# S06_Sensors.net
KiCad netlist of a schematic drawn in Altium Designer
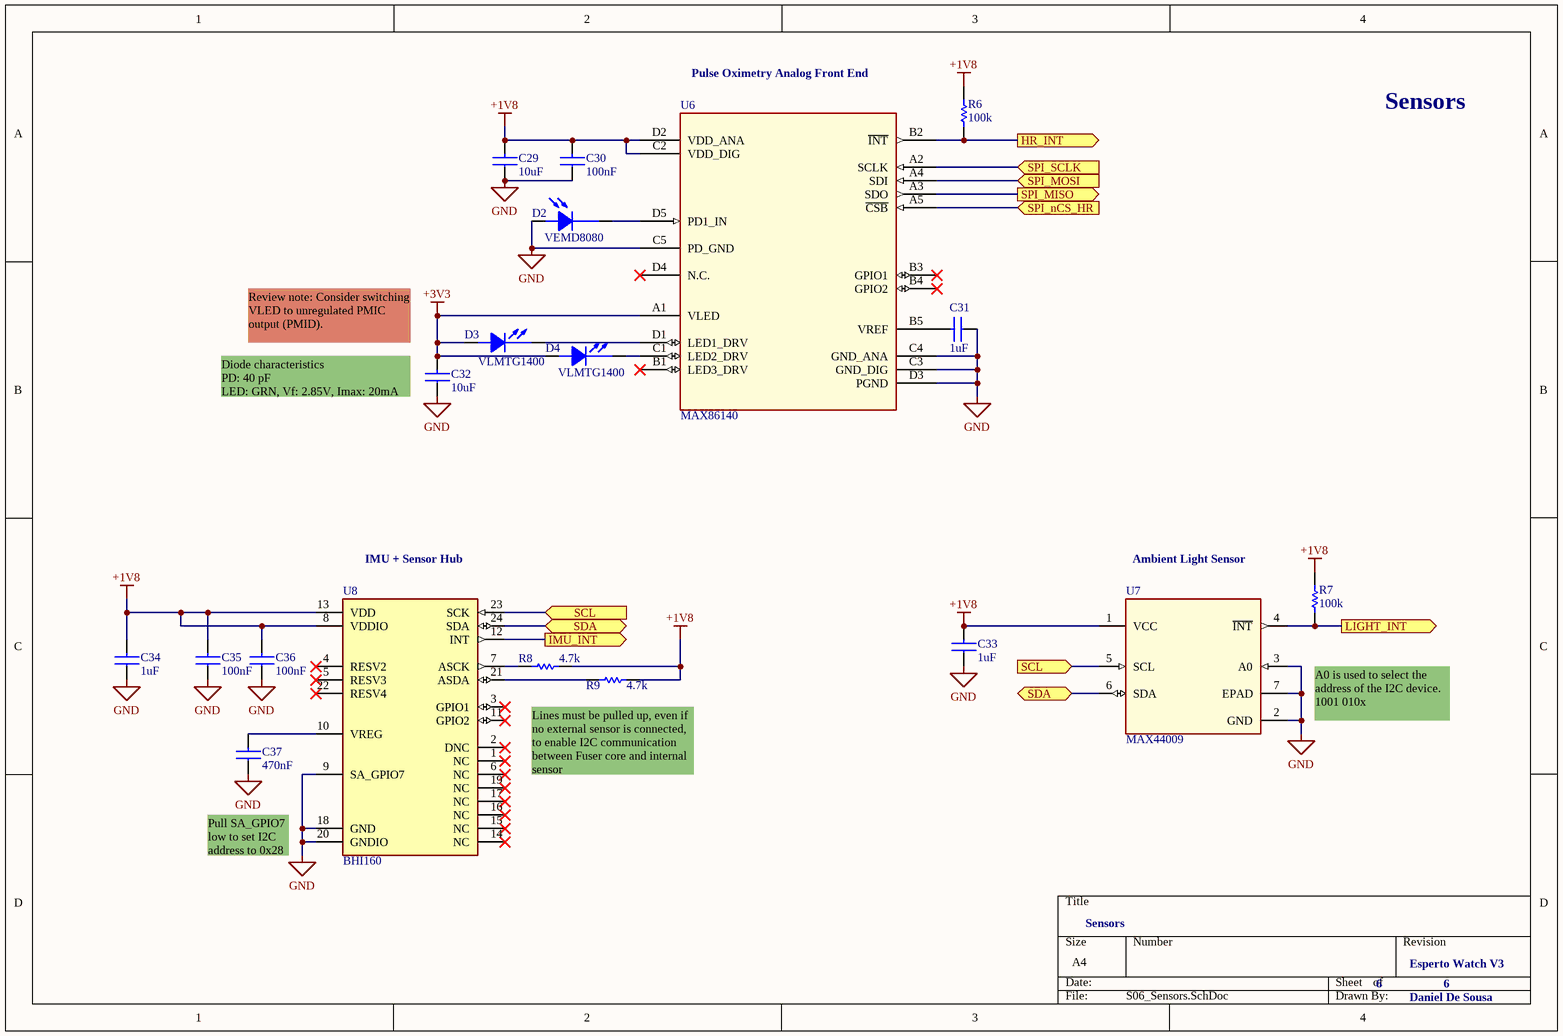
[diagram p0: S06_Sensors.SchDoc]

(export (version "E")
  (design (tool "Eeschema 10.0.6"))
  (components
    (comp (ref "C29")
      (value "10uF")
      (footprint "CC_1005_0402_N")
      (description "Capacitor")
      (libsource (lib "Esperto") (part "Capacitor"))
    )
    (comp (ref "C30")
      (value "100nF")
      (footprint "CC_1005_0402_N")
      (description "Capacitor")
      (libsource (lib "Esperto") (part "Capacitor"))
    )
    (comp (ref "C31")
      (value "1uF")
      (footprint "CC_1005_0402_N")
      (description "Capacitor")
      (libsource (lib "Esperto") (part "Capacitor"))
    )
    (comp (ref "C32")
      (value "10uF")
      (footprint "CC_1005_0402_N")
      (description "Capacitor")
      (libsource (lib "Esperto") (part "Capacitor"))
    )
    (comp (ref "C33")
      (value "1uF")
      (footprint "CC_1005_0402_N")
      (description "Capacitor")
      (libsource (lib "Esperto") (part "Capacitor"))
    )
    (comp (ref "C34")
      (value "1uF")
      (footprint "CC_1005_0402_N")
      (description "Capacitor")
      (libsource (lib "Esperto") (part "Capacitor"))
    )
    (comp (ref "C35")
      (value "100nF")
      (footprint "CC_1005_0402_N")
      (description "Capacitor")
      (libsource (lib "Esperto") (part "Capacitor"))
    )
    (comp (ref "C36")
      (value "100nF")
      (footprint "CC_1005_0402_N")
      (description "Capacitor")
      (libsource (lib "Esperto") (part "Capacitor"))
    )
    (comp (ref "C37")
      (value "470nF")
      (footprint "CC_1005_0402_N")
      (description "Capacitor")
      (libsource (lib "Esperto") (part "Capacitor"))
    )
    (comp (ref "D2")
      (value "VEMD8080")
      (footprint "VEMD8080")
      (description "Photodiode")
      (libsource (lib "Esperto") (part "Photodiode"))
    )
    (comp (ref "D3")
      (value "VLMTG1400")
      (footprint "LED_GREEN_0603")
      (description "Single LED")
      (libsource (lib "Esperto") (part "LED"))
    )
    (comp (ref "D4")
      (value "VLMTG1400")
      (footprint "LED_GREEN_0603")
      (description "Single LED")
      (libsource (lib "Esperto") (part "LED"))
    )
    (comp (ref "R6")
      (value "100k")
      (footprint "RC_1005_0402_N")
      (description "Resistor")
      (libsource (lib "Esperto") (part "Resistor"))
    )
    (comp (ref "R7")
      (value "100k")
      (footprint "RC_1005_0402_N")
      (description "Resistor")
      (libsource (lib "Esperto") (part "Resistor"))
    )
    (comp (ref "R8")
      (value "4.7k")
      (footprint "RC_1005_0402_N")
      (description "Resistor")
      (libsource (lib "Esperto") (part "Resistor"))
    )
    (comp (ref "R9")
      (value "4.7k")
      (footprint "RC_1005_0402_N")
      (description "Resistor")
      (libsource (lib "Esperto") (part "Resistor"))
    )
    (comp (ref "U6")
      (value "MAX86140")
      (footprint "MAX86140")
      (description "Optical Pulse Oximeter and\r\nHeart-Rate Sensor")
      (fields
        (field (name "MANUFACTURER_PART_NUMBER") "MAX86140ENP+")
        (field (name "COPYRIGHT") "Copyright (C) 2018 Accelerated Designs. All rights reserved")
      )
      (libsource (lib "Esperto") (part "MAX86140"))
    )
    (comp (ref "U7")
      (value "MAX44009")
      (footprint "MAX44009")
      (description "Ambient Light Sensor")
      (fields
        (field (name "MANUFACTURER_PART_NUMBER") "MAX44009EDT+T")
        (field (name "COPYRIGHT") "Copyright (C) 2018 Accelerated Designs. All rights reserved")
      )
      (libsource (lib "Esperto") (part "MAX44009"))
    )
    (comp (ref "U8")
      (value "BHI160")
      (footprint "BHI160")
      (description "Ultra low-power sensor hub incl. integrated IMU")
      (fields (field (name "PROVIDED BY") "BOSCH"))
      (libsource (lib "Esperto") (part "BHI160"))
    )
  )
  (nets
    (net (code "1") (name "+1V8") (class "Default")
      (node (ref "C29") (pin "2") (pinfunction "2_2") (pintype "passive"))
      (node (ref "C30") (pin "2") (pinfunction "2_2") (pintype "passive"))
      (node (ref "C33") (pin "2") (pinfunction "2_2") (pintype "passive"))
      (node (ref "C34") (pin "2") (pinfunction "2_2") (pintype "passive"))
      (node (ref "C35") (pin "2") (pinfunction "2_2") (pintype "passive"))
      (node (ref "C36") (pin "2") (pinfunction "2_2") (pintype "passive"))
      (node (ref "R6") (pin "2") (pinfunction "2_2") (pintype "passive"))
      (node (ref "R7") (pin "2") (pinfunction "2_2") (pintype "passive"))
      (node (ref "R8") (pin "1") (pinfunction "1_1") (pintype "passive"))
      (node (ref "R9") (pin "1") (pinfunction "1_1") (pintype "passive"))
      (node (ref "U6") (pin "C2") (pinfunction "VDD_DIG_C2") (pintype "power_in"))
      (node (ref "U6") (pin "D2") (pinfunction "VDD_ANA_D2") (pintype "power_in"))
      (node (ref "U7") (pin "1") (pinfunction "VCC_1") (pintype "power_in"))
      (node (ref "U8") (pin "13") (pinfunction "VDD_13") (pintype "power_in"))
      (node (ref "U8") (pin "8") (pinfunction "VDDIO_8") (pintype "power_in"))
    )
    (net (code "2") (name "+3V3") (class "Default")
      (node (ref "C32") (pin "2") (pinfunction "2_2") (pintype "passive"))
      (node (ref "D3") (pin "A") (pinfunction "Anode_A") (pintype "passive"))
      (node (ref "D4") (pin "A") (pinfunction "Anode_A") (pintype "passive"))
      (node (ref "U6") (pin "A1") (pinfunction "VLED_A1") (pintype "passive"))
    )
    (net (code "3") (name "/HR_INT") (class "Default")
      (node (ref "R6") (pin "1") (pinfunction "1_1") (pintype "passive"))
      (node (ref "U6") (pin "B2") (pinfunction "~{INT}_B2") (pintype "output"))
    )
    (net (code "4") (name "/IMU_INT") (class "Default")
      (node (ref "U8") (pin "12") (pinfunction "INT_12") (pintype "output"))
    )
    (net (code "5") (name "/LIGHT_INT") (class "Default")
      (node (ref "R7") (pin "1") (pinfunction "1_1") (pintype "passive"))
      (node (ref "U7") (pin "4") (pinfunction "~{INT}_4") (pintype "output"))
    )
    (net (code "6") (name "/SCL") (class "Default")
      (node (ref "U7") (pin "5") (pinfunction "SCL_5") (pintype "input"))
      (node (ref "U8") (pin "23") (pinfunction "SCK_23") (pintype "input"))
    )
    (net (code "7") (name "/SDA") (class "Default")
      (node (ref "U7") (pin "6") (pinfunction "SDA_6") (pintype "bidirectional"))
      (node (ref "U8") (pin "24") (pinfunction "SDA_24") (pintype "bidirectional"))
    )
    (net (code "8") (name "/SPI_MISO") (class "Default")
      (node (ref "U6") (pin "A3") (pinfunction "SDO_A3") (pintype "output"))
    )
    (net (code "9") (name "/SPI_MOSI") (class "Default")
      (node (ref "U6") (pin "A4") (pinfunction "SDI_A4") (pintype "input"))
    )
    (net (code "10") (name "/SPI_SCLK") (class "Default")
      (node (ref "U6") (pin "A2") (pinfunction "SCLK_A2") (pintype "input"))
    )
    (net (code "11") (name "/SPI_nCS_HR") (class "Default")
      (node (ref "U6") (pin "A5") (pinfunction "~{CSB}_A5") (pintype "input"))
    )
    (net (code "12") (name "GND") (class "Default")
      (node (ref "C29") (pin "1") (pinfunction "1_1") (pintype "passive"))
      (node (ref "C30") (pin "1") (pinfunction "1_1") (pintype "passive"))
      (node (ref "C31") (pin "1") (pinfunction "1_1") (pintype "passive"))
      (node (ref "C32") (pin "1") (pinfunction "1_1") (pintype "passive"))
      (node (ref "C33") (pin "1") (pinfunction "1_1") (pintype "passive"))
      (node (ref "C34") (pin "1") (pinfunction "1_1") (pintype "passive"))
      (node (ref "C35") (pin "1") (pinfunction "1_1") (pintype "passive"))
      (node (ref "C36") (pin "1") (pinfunction "1_1") (pintype "passive"))
      (node (ref "C37") (pin "1") (pinfunction "1_1") (pintype "passive"))
      (node (ref "D2") (pin "A") (pinfunction "Anode_A") (pintype "passive"))
      (node (ref "U6") (pin "C3") (pinfunction "GND_DIG_C3") (pintype "passive"))
      (node (ref "U6") (pin "C4") (pinfunction "GND_ANA_C4") (pintype "passive"))
      (node (ref "U6") (pin "C5") (pinfunction "PD_GND_C5") (pintype "passive"))
      (node (ref "U6") (pin "D3") (pinfunction "PGND_D3") (pintype "passive"))
      (node (ref "U7") (pin "2") (pinfunction "GND_2") (pintype "power_in"))
      (node (ref "U7") (pin "3") (pinfunction "A0_3") (pintype "input"))
      (node (ref "U7") (pin "7") (pinfunction "EPAD_7") (pintype "power_in"))
      (node (ref "U8") (pin "18") (pinfunction "GND_18") (pintype "power_in"))
      (node (ref "U8") (pin "20") (pinfunction "GNDIO_20") (pintype "power_in"))
      (node (ref "U8") (pin "9") (pinfunction "SA_GPIO7_9") (pintype "passive"))
    )
    (net (code "13") (name "Net-(D2-Cathode)") (class "Default")
      (node (ref "D2") (pin "K") (pinfunction "Cathode_K") (pintype "passive"))
      (node (ref "U6") (pin "D5") (pinfunction "PD1_IN_D5") (pintype "input"))
    )
    (net (code "14") (name "Net-(D3-Cathode)") (class "Default")
      (node (ref "D3") (pin "K") (pinfunction "Cathode_K") (pintype "passive"))
      (node (ref "U6") (pin "D1") (pinfunction "LED1_DRV_D1") (pintype "bidirectional"))
    )
    (net (code "15") (name "Net-(D4-Cathode)") (class "Default")
      (node (ref "D4") (pin "K") (pinfunction "Cathode_K") (pintype "passive"))
      (node (ref "U6") (pin "C1") (pinfunction "LED2_DRV_C1") (pintype "bidirectional"))
    )
    (net (code "16") (name "Net-(U6-VREF)") (class "Default")
      (node (ref "C31") (pin "2") (pinfunction "2_2") (pintype "passive"))
      (node (ref "U6") (pin "B5") (pinfunction "VREF_B5") (pintype "power_in"))
    )
    (net (code "17") (name "Net-(U8-ASCK)") (class "Default")
      (node (ref "R8") (pin "2") (pinfunction "2_2") (pintype "passive"))
      (node (ref "U8") (pin "7") (pinfunction "ASCK_7") (pintype "output"))
    )
    (net (code "18") (name "Net-(U8-ASDA)") (class "Default")
      (node (ref "R9") (pin "2") (pinfunction "2_2") (pintype "passive"))
      (node (ref "U8") (pin "21") (pinfunction "ASDA_21") (pintype "bidirectional"))
    )
    (net (code "19") (name "Net-(U8-VREG)") (class "Default")
      (node (ref "C37") (pin "2") (pinfunction "2_2") (pintype "passive"))
      (node (ref "U8") (pin "10") (pinfunction "VREG_10") (pintype "power_in"))
    )
    (net (code "20") (name "unconnected-(U6-GPIO1-PadB3)") (class "Default")
      (node (ref "U6") (pin "B3") (pinfunction "GPIO1_B3") (pintype "bidirectional+no_connect"))
    )
    (net (code "21") (name "unconnected-(U6-GPIO2-PadB4)") (class "Default")
      (node (ref "U6") (pin "B4") (pinfunction "GPIO2_B4") (pintype "bidirectional+no_connect"))
    )
    (net (code "22") (name "unconnected-(U6-LED3_DRV-PadB1)") (class "Default")
      (node (ref "U6") (pin "B1") (pinfunction "LED3_DRV_B1") (pintype "bidirectional+no_connect"))
    )
    (net (code "23") (name "unconnected-(U6-N.C.-PadD4)") (class "Default")
      (node (ref "U6") (pin "D4") (pinfunction "N.C._D4") (pintype "passive+no_connect"))
    )
    (net (code "24") (name "unconnected-(U8-DNC-Pad2)") (class "Default")
      (node (ref "U8") (pin "2") (pinfunction "DNC_2") (pintype "passive+no_connect"))
    )
    (net (code "25") (name "unconnected-(U8-GPIO1-Pad3)") (class "Default")
      (node (ref "U8") (pin "3") (pinfunction "GPIO1_3") (pintype "bidirectional+no_connect"))
    )
    (net (code "26") (name "unconnected-(U8-GPIO2-Pad11)") (class "Default")
      (node (ref "U8") (pin "11") (pinfunction "GPIO2_11") (pintype "bidirectional+no_connect"))
    )
    (net (code "27") (name "unconnected-(U8-NC-Pad1)") (class "Default")
      (node (ref "U8") (pin "1") (pinfunction "NC_1") (pintype "passive+no_connect"))
    )
    (net (code "28") (name "unconnected-(U8-NC-Pad6)") (class "Default")
      (node (ref "U8") (pin "6") (pinfunction "NC_6") (pintype "passive+no_connect"))
    )
    (net (code "29") (name "unconnected-(U8-NC-Pad14)") (class "Default")
      (node (ref "U8") (pin "14") (pinfunction "NC_14") (pintype "passive+no_connect"))
    )
    (net (code "30") (name "unconnected-(U8-NC-Pad15)") (class "Default")
      (node (ref "U8") (pin "15") (pinfunction "NC_15") (pintype "passive+no_connect"))
    )
    (net (code "31") (name "unconnected-(U8-NC-Pad16)") (class "Default")
      (node (ref "U8") (pin "16") (pinfunction "NC_16") (pintype "passive+no_connect"))
    )
    (net (code "32") (name "unconnected-(U8-NC-Pad17)") (class "Default")
      (node (ref "U8") (pin "17") (pinfunction "NC_17") (pintype "passive+no_connect"))
    )
    (net (code "33") (name "unconnected-(U8-NC-Pad19)") (class "Default")
      (node (ref "U8") (pin "19") (pinfunction "NC_19") (pintype "passive+no_connect"))
    )
    (net (code "34") (name "unconnected-(U8-RESV2-Pad4)") (class "Default")
      (node (ref "U8") (pin "4") (pinfunction "RESV2_4") (pintype "passive+no_connect"))
    )
    (net (code "35") (name "unconnected-(U8-RESV3-Pad5)") (class "Default")
      (node (ref "U8") (pin "5") (pinfunction "RESV3_5") (pintype "passive+no_connect"))
    )
    (net (code "36") (name "unconnected-(U8-RESV4-Pad22)") (class "Default")
      (node (ref "U8") (pin "22") (pinfunction "RESV4_22") (pintype "passive+no_connect"))
    )
  )
)
